# ESP32.net
KiCad netlist of a schematic drawn in Altium Designer
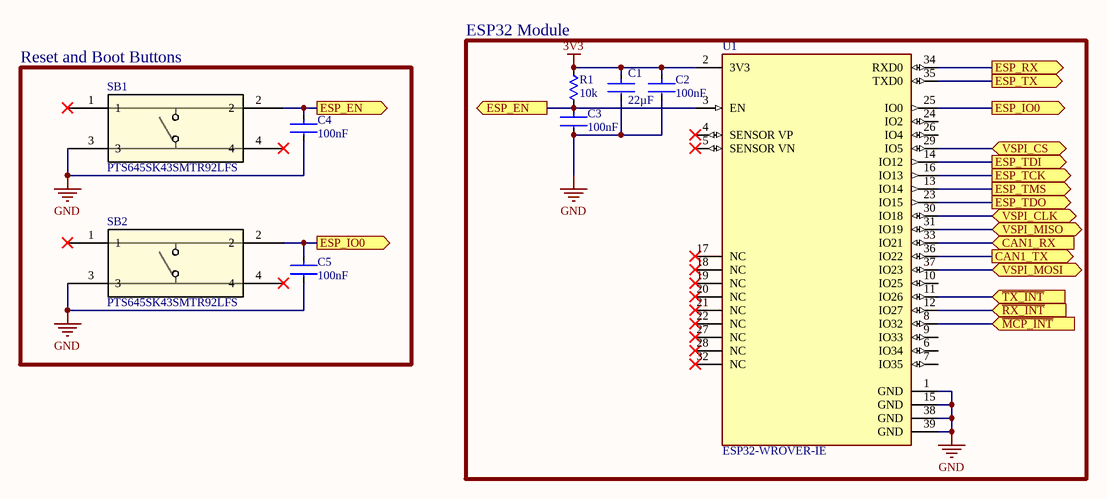
[diagram p0: ESP32.SchDoc]

(export (version "E")
  (design (tool "Eeschema 10.0.6"))
  (components
    (comp (ref "C1")
      (value "22µF")
      (footprint "CL32A226KAJNNNE-Footprint-1")
      (fields (field (name "TOLERANCE") "10%") (field (name "Comment") "CL32A226KAJNNNE"))
      (libsource (lib "UCalgary Racing - Power Electronics") (part "CAPACITOR"))
    )
    (comp (ref "C2")
      (value "100nF")
      (footprint "FP-CL10-IPC_B")
      (description "0.1 µF ±10% 50V Ceramic Capacitor X7R 0603 (1608 Metric)")
      (fields (field (name "Comment") "CL10B104KB8WPNC"))
      (libsource (lib "UCalgary Racing - Power Electronics") (part "CAPACITOR"))
    )
    (comp (ref "C3")
      (value "100nF")
      (footprint "FP-CL10-IPC_B")
      (description "0.1 µF ±10% 50V Ceramic Capacitor X7R 0603 (1608 Metric)")
      (fields (field (name "Comment") "CL10B104KB8WPNC"))
      (libsource (lib "UCalgary Racing - Power Electronics") (part "CAPACITOR"))
    )
    (comp (ref "C4")
      (value "100nF")
      (footprint "FP-CL10-IPC_B")
      (description "0.1 µF ±10% 50V Ceramic Capacitor X7R 0603 (1608 Metric)")
      (fields (field (name "Comment") "CL10B104KB8WPNC"))
      (libsource (lib "UCalgary Racing - Power Electronics") (part "CAPACITOR"))
    )
    (comp (ref "C5")
      (value "100nF")
      (footprint "FP-CL10-IPC_B")
      (description "0.1 µF ±10% 50V Ceramic Capacitor X7R 0603 (1608 Metric)")
      (fields (field (name "Comment") "CL10B104KB8WPNC"))
      (libsource (lib "UCalgary Racing - Power Electronics") (part "CAPACITOR"))
    )
    (comp (ref "R1")
      (value "10k")
      (footprint "FP-CRCW0603-e3-IPC_B")
      (description "10 kOhms ±1% 0.1W, 1/10W Chip Resistor 0603 (1608 Metric) Automotive AEC-Q200 Thick Film")
      (fields (field (name "POWER") "100mW") (field (name "TOLERANCE") "1%"))
      (libsource (lib "UCalgary Racing - Power Electronics") (part "RESISTOR"))
    )
    (comp (ref "SB1")
      (value "PTS645SK43SMTR92LFS")
      (footprint "PTS645SK43SMTR92LFS-Footprint-1")
      (libsource (lib "UCalgary Racing - Power Electronics") (part "PTS645SK43SMTR92LFS-Symbol-1"))
    )
    (comp (ref "SB2")
      (value "PTS645SK43SMTR92LFS")
      (footprint "PTS645SK43SMTR92LFS-Footprint-1")
      (libsource (lib "UCalgary Racing - Power Electronics") (part "PTS645SK43SMTR92LFS-Symbol-1"))
    )
    (comp (ref "U1")
      (value "ESP32-WROVER-IE")
      (footprint "FP-ESP32-WROVER-IE_M213EH-MFG")
      (description "Rx Txrx Mod Wifi Ext Ipex SMD")
      (libsource (lib "UCalgary Racing - Power Electronics") (part "4b5fa60a9c1738a7ea1a024bf8731a9"))
    )
  )
  (nets
    (net (code "1") (name "/CAN1_RX") (class "Default")
      (node (ref "U1") (pin "33") (pinfunction "IO21_33") (pintype "bidirectional"))
    )
    (net (code "2") (name "/CAN1_TX") (class "Default")
      (node (ref "U1") (pin "36") (pinfunction "IO22_36") (pintype "bidirectional"))
    )
    (net (code "3") (name "/ESP_EN") (class "Default")
      (node (ref "C3") (pin "1") (pinfunction "1_1") (pintype "passive"))
      (node (ref "C4") (pin "1") (pinfunction "1_1") (pintype "passive"))
      (node (ref "R1") (pin "1") (pinfunction "1_1") (pintype "passive"))
      (node (ref "SB1") (pin "2") (pinfunction "2_2") (pintype "passive"))
      (node (ref "U1") (pin "3") (pinfunction "EN_3") (pintype "input"))
    )
    (net (code "4") (name "/ESP_IO0") (class "Default")
      (node (ref "C5") (pin "1") (pinfunction "1_1") (pintype "passive"))
      (node (ref "SB2") (pin "2") (pinfunction "2_2") (pintype "passive"))
      (node (ref "U1") (pin "25") (pinfunction "IO0_25") (pintype "output"))
    )
    (net (code "5") (name "/ESP_RX") (class "Default")
      (node (ref "U1") (pin "34") (pinfunction "RXD0_34") (pintype "bidirectional"))
    )
    (net (code "6") (name "/ESP_TCK") (class "Default")
      (node (ref "U1") (pin "16") (pinfunction "IO13_16") (pintype "output"))
    )
    (net (code "7") (name "/ESP_TDI") (class "Default")
      (node (ref "U1") (pin "14") (pinfunction "IO12_14") (pintype "output"))
    )
    (net (code "8") (name "/ESP_TDO") (class "Default")
      (node (ref "U1") (pin "23") (pinfunction "IO15_23") (pintype "output"))
    )
    (net (code "9") (name "/ESP_TMS") (class "Default")
      (node (ref "U1") (pin "13") (pinfunction "IO14_13") (pintype "output"))
    )
    (net (code "10") (name "/ESP_TX") (class "Default")
      (node (ref "U1") (pin "35") (pinfunction "TXD0_35") (pintype "bidirectional"))
    )
    (net (code "11") (name "/MCP_INT") (class "Default")
      (node (ref "U1") (pin "8") (pinfunction "IO32_8") (pintype "bidirectional"))
    )
    (net (code "12") (name "/RX_INT") (class "Default")
      (node (ref "U1") (pin "12") (pinfunction "IO27_12") (pintype "bidirectional"))
    )
    (net (code "13") (name "/TX_INT") (class "Default")
      (node (ref "U1") (pin "11") (pinfunction "IO26_11") (pintype "bidirectional"))
    )
    (net (code "14") (name "/VSPI_CLK") (class "Default")
      (node (ref "U1") (pin "30") (pinfunction "IO18_30") (pintype "bidirectional"))
    )
    (net (code "15") (name "/VSPI_CS") (class "Default")
      (node (ref "U1") (pin "29") (pinfunction "IO5_29") (pintype "bidirectional"))
    )
    (net (code "16") (name "/VSPI_MISO") (class "Default")
      (node (ref "U1") (pin "31") (pinfunction "IO19_31") (pintype "bidirectional"))
    )
    (net (code "17") (name "/VSPI_MOSI") (class "Default")
      (node (ref "U1") (pin "37") (pinfunction "IO23_37") (pintype "bidirectional"))
    )
    (net (code "18") (name "3V3") (class "Default")
      (node (ref "C1") (pin "1") (pinfunction "1_1") (pintype "passive"))
      (node (ref "C2") (pin "1") (pinfunction "1_1") (pintype "passive"))
      (node (ref "R1") (pin "2") (pinfunction "2_2") (pintype "passive"))
      (node (ref "U1") (pin "2") (pinfunction "3V3_2") (pintype "passive"))
    )
    (net (code "19") (name "GND") (class "Default")
      (node (ref "C1") (pin "2") (pinfunction "2_2") (pintype "passive"))
      (node (ref "C2") (pin "2") (pinfunction "2_2") (pintype "passive"))
      (node (ref "C3") (pin "2") (pinfunction "2_2") (pintype "passive"))
      (node (ref "C4") (pin "2") (pinfunction "2_2") (pintype "passive"))
      (node (ref "C5") (pin "2") (pinfunction "2_2") (pintype "passive"))
      (node (ref "SB1") (pin "3") (pinfunction "3_3") (pintype "passive"))
      (node (ref "SB2") (pin "3") (pinfunction "3_3") (pintype "passive"))
      (node (ref "U1") (pin "1") (pinfunction "GND_1") (pintype "power_in"))
      (node (ref "U1") (pin "15") (pinfunction "GND_15") (pintype "power_in"))
      (node (ref "U1") (pin "38") (pinfunction "GND_38") (pintype "power_in"))
      (node (ref "U1") (pin "39") (pinfunction "GND_39") (pintype "power_in"))
    )
    (net (code "20") (name "unconnected-(SB1-Pad1)") (class "Default")
      (node (ref "SB1") (pin "1") (pinfunction "1_1") (pintype "passive+no_connect"))
    )
    (net (code "21") (name "unconnected-(SB1-Pad4)") (class "Default")
      (node (ref "SB1") (pin "4") (pinfunction "4_4") (pintype "passive+no_connect"))
    )
    (net (code "22") (name "unconnected-(SB2-Pad1)") (class "Default")
      (node (ref "SB2") (pin "1") (pinfunction "1_1") (pintype "passive+no_connect"))
    )
    (net (code "23") (name "unconnected-(SB2-Pad4)") (class "Default")
      (node (ref "SB2") (pin "4") (pinfunction "4_4") (pintype "passive+no_connect"))
    )
    (net (code "24") (name "unconnected-(U1-IO2-Pad24)") (class "Default")
      (node (ref "U1") (pin "24") (pinfunction "IO2_24") (pintype "bidirectional"))
    )
    (net (code "25") (name "unconnected-(U1-IO4-Pad26)") (class "Default")
      (node (ref "U1") (pin "26") (pinfunction "IO4_26") (pintype "bidirectional"))
    )
    (net (code "26") (name "unconnected-(U1-IO25-Pad10)") (class "Default")
      (node (ref "U1") (pin "10") (pinfunction "IO25_10") (pintype "bidirectional"))
    )
    (net (code "27") (name "unconnected-(U1-IO33-Pad9)") (class "Default")
      (node (ref "U1") (pin "9") (pinfunction "IO33_9") (pintype "bidirectional"))
    )
    (net (code "28") (name "unconnected-(U1-IO34-Pad6)") (class "Default")
      (node (ref "U1") (pin "6") (pinfunction "IO34_6") (pintype "bidirectional"))
    )
    (net (code "29") (name "unconnected-(U1-IO35-Pad7)") (class "Default")
      (node (ref "U1") (pin "7") (pinfunction "IO35_7") (pintype "bidirectional"))
    )
    (net (code "30") (name "unconnected-(U1-NC-Pad17)") (class "Default")
      (node (ref "U1") (pin "17") (pinfunction "NC_17") (pintype "passive+no_connect"))
    )
    (net (code "31") (name "unconnected-(U1-NC-Pad18)") (class "Default")
      (node (ref "U1") (pin "18") (pinfunction "NC_18") (pintype "passive+no_connect"))
    )
    (net (code "32") (name "unconnected-(U1-NC-Pad19)") (class "Default")
      (node (ref "U1") (pin "19") (pinfunction "NC_19") (pintype "passive+no_connect"))
    )
    (net (code "33") (name "unconnected-(U1-NC-Pad20)") (class "Default")
      (node (ref "U1") (pin "20") (pinfunction "NC_20") (pintype "passive+no_connect"))
    )
    (net (code "34") (name "unconnected-(U1-NC-Pad21)") (class "Default")
      (node (ref "U1") (pin "21") (pinfunction "NC_21") (pintype "passive+no_connect"))
    )
    (net (code "35") (name "unconnected-(U1-NC-Pad22)") (class "Default")
      (node (ref "U1") (pin "22") (pinfunction "NC_22") (pintype "passive+no_connect"))
    )
    (net (code "36") (name "unconnected-(U1-NC-Pad27)") (class "Default")
      (node (ref "U1") (pin "27") (pinfunction "NC_27") (pintype "passive+no_connect"))
    )
    (net (code "37") (name "unconnected-(U1-NC-Pad28)") (class "Default")
      (node (ref "U1") (pin "28") (pinfunction "NC_28") (pintype "passive+no_connect"))
    )
    (net (code "38") (name "unconnected-(U1-NC-Pad32)") (class "Default")
      (node (ref "U1") (pin "32") (pinfunction "NC_32") (pintype "passive+no_connect"))
    )
    (net (code "39") (name "unconnected-(U1-SENSOR_VN-Pad5)") (class "Default")
      (node (ref "U1") (pin "5") (pinfunction "SENSOR_VN_5") (pintype "bidirectional+no_connect"))
    )
    (net (code "40") (name "unconnected-(U1-SENSOR_VP-Pad4)") (class "Default")
      (node (ref "U1") (pin "4") (pinfunction "SENSOR_VP_4") (pintype "bidirectional+no_connect"))
    )
  )
)
